# motordriver.net
KiCad netlist of a schematic drawn in EAGLE
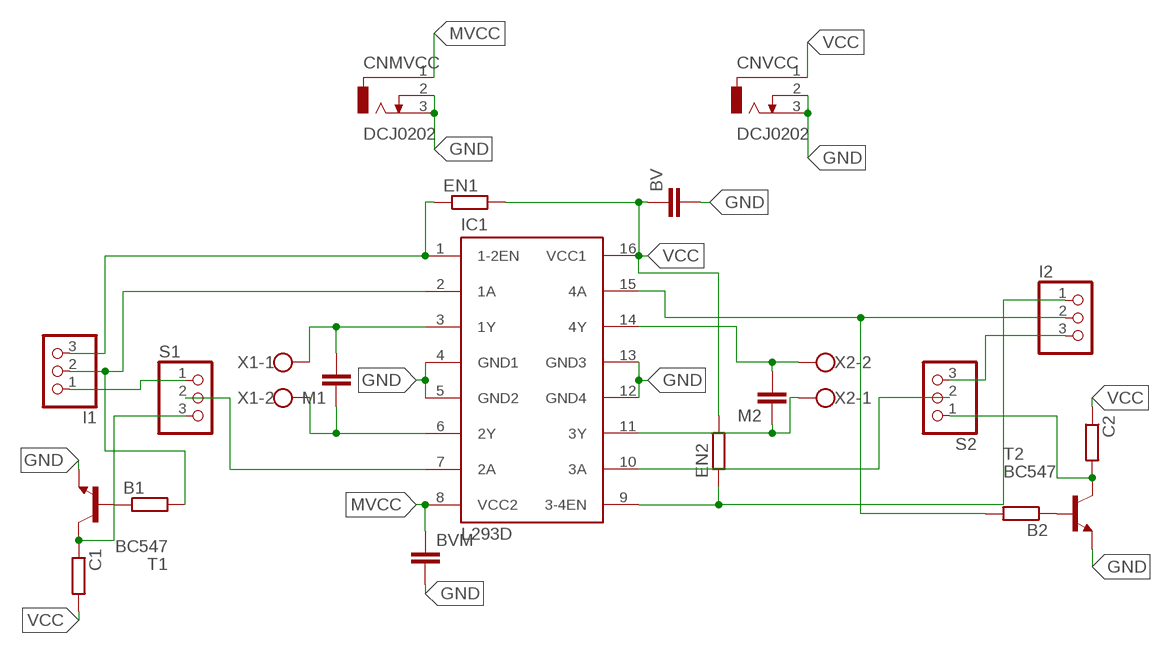
[diagram p0: schematic, sheet 1]

(export (version "E")
  (design (tool "Eeschema 10.0.6"))
  (components
    (comp (ref "B1")
      (value "R-EU_0204/7")
      (footprint "eagle-import:0204_7")
      (libsource (lib "eagle-import") (part "R-EU_0204/7"))
    )
    (comp (ref "B2")
      (value "R-EU_0204/7")
      (footprint "eagle-import:0204_7")
      (libsource (lib "eagle-import") (part "R-EU_0204/7"))
    )
    (comp (ref "BV")
      (value "C2.5/2")
      (footprint "eagle-import:C2.5-2")
      (libsource (lib "eagle-import") (part "C2.5/2"))
    )
    (comp (ref "BVM")
      (value "C-EU050-025X075")
      (footprint "eagle-import:C050-025X075")
      (libsource (lib "eagle-import") (part "C-EU050-025X075"))
    )
    (comp (ref "C1")
      (value "R-EU_0204/7")
      (footprint "eagle-import:0204_7")
      (libsource (lib "eagle-import") (part "R-EU_0204/7"))
    )
    (comp (ref "C2")
      (value "R-EU_0204/7")
      (footprint "eagle-import:0204_7")
      (libsource (lib "eagle-import") (part "R-EU_0204/7"))
    )
    (comp (ref "CNMVCC")
      (value "DCJ0202")
      (footprint "eagle-import:DCJ0202")
      (libsource (lib "eagle-import") (part "DCJ0202"))
    )
    (comp (ref "CNVCC")
      (value "DCJ0202")
      (footprint "eagle-import:DCJ0202")
      (libsource (lib "eagle-import") (part "DCJ0202"))
    )
    (comp (ref "EN1")
      (value "R-EU_0204/7")
      (footprint "eagle-import:0204_7")
      (libsource (lib "eagle-import") (part "R-EU_0204/7"))
    )
    (comp (ref "EN2")
      (value "R-EU_0204/7")
      (footprint "eagle-import:0204_7")
      (libsource (lib "eagle-import") (part "R-EU_0204/7"))
    )
    (comp (ref "I1")
      (value "PINHD-1X3")
      (footprint "eagle-import:1X03")
      (libsource (lib "eagle-import") (part "PINHD-1X3"))
    )
    (comp (ref "I2")
      (value "PINHD-1X3")
      (footprint "eagle-import:1X03")
      (libsource (lib "eagle-import") (part "PINHD-1X3"))
    )
    (comp (ref "IC1")
      (value "L293D")
      (footprint "eagle-import:DIL16")
      (libsource (lib "eagle-import") (part "L293D"))
    )
    (comp (ref "M1")
      (value "C2.5/2")
      (footprint "eagle-import:C2.5-2")
      (libsource (lib "eagle-import") (part "C2.5/2"))
    )
    (comp (ref "M2")
      (value "C2.5/2")
      (footprint "eagle-import:C2.5-2")
      (libsource (lib "eagle-import") (part "C2.5/2"))
    )
    (comp (ref "S1")
      (value "PINHD-1X3")
      (footprint "eagle-import:1X03")
      (libsource (lib "eagle-import") (part "PINHD-1X3"))
    )
    (comp (ref "S2")
      (value "PINHD-1X3")
      (footprint "eagle-import:1X03")
      (libsource (lib "eagle-import") (part "PINHD-1X3"))
    )
    (comp (ref "T1")
      (value "BC547")
      (footprint "eagle-import:TO92")
      (libsource (lib "eagle-import") (part "BC547"))
    )
    (comp (ref "T2")
      (value "BC547")
      (footprint "eagle-import:TO92")
      (libsource (lib "eagle-import") (part "BC547"))
    )
    (comp (ref "X1")
      (value "W237-102")
      (footprint "eagle-import:W237-102")
      (fields (field (name "MPN") "237-102"))
      (libsource (lib "eagle-import") (part "W237-102"))
    )
    (comp (ref "X2")
      (value "W237-102")
      (footprint "eagle-import:W237-102")
      (fields (field (name "MPN") "237-102"))
      (libsource (lib "eagle-import") (part "W237-102"))
    )
  )
  (nets
    (net (code "1") (name "GND") (class "Default")
      (node (ref "BV") (pin "2") (pinfunction "2_2") (pintype "passive"))
      (node (ref "BVM") (pin "2") (pinfunction "2_2") (pintype "passive"))
      (node (ref "CNMVCC") (pin "2") (pinfunction "2_2") (pintype "passive"))
      (node (ref "CNMVCC") (pin "3") (pinfunction "3_3") (pintype "passive"))
      (node (ref "CNVCC") (pin "2") (pinfunction "2_2") (pintype "passive"))
      (node (ref "CNVCC") (pin "3") (pinfunction "3_3") (pintype "passive"))
      (node (ref "IC1") (pin "12") (pinfunction "GND4_12") (pintype "power_in"))
      (node (ref "IC1") (pin "13") (pinfunction "GND3_13") (pintype "power_in"))
      (node (ref "IC1") (pin "4") (pinfunction "GND1_4") (pintype "power_in"))
      (node (ref "IC1") (pin "5") (pinfunction "GND2_5") (pintype "power_in"))
      (node (ref "T1") (pin "1") (pinfunction "E_1") (pintype "passive"))
      (node (ref "T2") (pin "1") (pinfunction "E_1") (pintype "passive"))
    )
    (net (code "2") (name "MVCC") (class "Default")
      (node (ref "BVM") (pin "1") (pinfunction "1_1") (pintype "passive"))
      (node (ref "CNMVCC") (pin "1") (pinfunction "1_1") (pintype "passive"))
      (node (ref "IC1") (pin "8") (pinfunction "VCC2_8") (pintype "power_in"))
    )
    (net (code "3") (name "Net-(I1-Pad1)") (class "Default")
      (node (ref "I1") (pin "1") (pinfunction "1_1") (pintype "passive"))
      (node (ref "S1") (pin "1") (pinfunction "1_1") (pintype "passive"))
    )
    (net (code "4") (name "Net-(I2-Pad3)") (class "Default")
      (node (ref "I2") (pin "3") (pinfunction "3_3") (pintype "passive"))
      (node (ref "S2") (pin "3") (pinfunction "3_3") (pintype "passive"))
    )
    (net (code "5") (name "Net-(IC1-1-2EN)") (class "Default")
      (node (ref "EN1") (pin "1") (pinfunction "1_1") (pintype "passive"))
      (node (ref "I1") (pin "3") (pinfunction "3_3") (pintype "passive"))
      (node (ref "IC1") (pin "1") (pinfunction "1-2EN_1") (pintype "input"))
    )
    (net (code "6") (name "Net-(IC1-1A)") (class "Default")
      (node (ref "B1") (pin "2") (pinfunction "2_2") (pintype "passive"))
      (node (ref "I1") (pin "2") (pinfunction "2_2") (pintype "passive"))
      (node (ref "IC1") (pin "2") (pinfunction "1A_2") (pintype "input"))
    )
    (net (code "7") (name "Net-(IC1-1Y)") (class "Default")
      (node (ref "IC1") (pin "3") (pinfunction "1Y_3") (pintype "output"))
      (node (ref "M1") (pin "2") (pinfunction "2_2") (pintype "passive"))
      (node (ref "X1") (pin "1") (pinfunction "KL_1") (pintype "passive"))
    )
    (net (code "8") (name "Net-(IC1-2A)") (class "Default")
      (node (ref "IC1") (pin "7") (pinfunction "2A_7") (pintype "input"))
      (node (ref "S1") (pin "2") (pinfunction "2_2") (pintype "passive"))
    )
    (net (code "9") (name "Net-(IC1-2Y)") (class "Default")
      (node (ref "IC1") (pin "6") (pinfunction "2Y_6") (pintype "output"))
      (node (ref "M1") (pin "1") (pinfunction "1_1") (pintype "passive"))
      (node (ref "X1") (pin "2") (pinfunction "KL_2") (pintype "passive"))
    )
    (net (code "10") (name "Net-(IC1-3-4EN)") (class "Default")
      (node (ref "EN2") (pin "1") (pinfunction "1_1") (pintype "passive"))
      (node (ref "I2") (pin "1") (pinfunction "1_1") (pintype "passive"))
      (node (ref "IC1") (pin "9") (pinfunction "3-4EN_9") (pintype "input"))
    )
    (net (code "11") (name "Net-(IC1-3A)") (class "Default")
      (node (ref "IC1") (pin "10") (pinfunction "3A_10") (pintype "input"))
      (node (ref "S2") (pin "2") (pinfunction "2_2") (pintype "passive"))
    )
    (net (code "12") (name "Net-(IC1-3Y)") (class "Default")
      (node (ref "IC1") (pin "11") (pinfunction "3Y_11") (pintype "output"))
      (node (ref "M2") (pin "1") (pinfunction "1_1") (pintype "passive"))
      (node (ref "X2") (pin "1") (pinfunction "KL_1") (pintype "passive"))
    )
    (net (code "13") (name "Net-(IC1-4A)") (class "Default")
      (node (ref "B2") (pin "2") (pinfunction "2_2") (pintype "passive"))
      (node (ref "I2") (pin "2") (pinfunction "2_2") (pintype "passive"))
      (node (ref "IC1") (pin "15") (pinfunction "4A_15") (pintype "input"))
    )
    (net (code "14") (name "Net-(IC1-4Y)") (class "Default")
      (node (ref "IC1") (pin "14") (pinfunction "4Y_14") (pintype "output"))
      (node (ref "M2") (pin "2") (pinfunction "2_2") (pintype "passive"))
      (node (ref "X2") (pin "2") (pinfunction "KL_2") (pintype "passive"))
    )
    (net (code "15") (name "Net-(T1-B)") (class "Default")
      (node (ref "B1") (pin "1") (pinfunction "1_1") (pintype "passive"))
      (node (ref "T1") (pin "2") (pinfunction "B_2") (pintype "passive"))
    )
    (net (code "16") (name "Net-(T1-C)") (class "Default")
      (node (ref "C1") (pin "1") (pinfunction "1_1") (pintype "passive"))
      (node (ref "S1") (pin "3") (pinfunction "3_3") (pintype "passive"))
      (node (ref "T1") (pin "3") (pinfunction "C_3") (pintype "passive"))
    )
    (net (code "17") (name "Net-(T2-B)") (class "Default")
      (node (ref "B2") (pin "1") (pinfunction "1_1") (pintype "passive"))
      (node (ref "T2") (pin "2") (pinfunction "B_2") (pintype "passive"))
    )
    (net (code "18") (name "Net-(T2-C)") (class "Default")
      (node (ref "C2") (pin "2") (pinfunction "2_2") (pintype "passive"))
      (node (ref "S2") (pin "1") (pinfunction "1_1") (pintype "passive"))
      (node (ref "T2") (pin "3") (pinfunction "C_3") (pintype "passive"))
    )
    (net (code "19") (name "VCC") (class "Default")
      (node (ref "BV") (pin "1") (pinfunction "1_1") (pintype "passive"))
      (node (ref "C1") (pin "2") (pinfunction "2_2") (pintype "passive"))
      (node (ref "C2") (pin "1") (pinfunction "1_1") (pintype "passive"))
      (node (ref "CNVCC") (pin "1") (pinfunction "1_1") (pintype "passive"))
      (node (ref "EN1") (pin "2") (pinfunction "2_2") (pintype "passive"))
      (node (ref "EN2") (pin "2") (pinfunction "2_2") (pintype "passive"))
      (node (ref "IC1") (pin "16") (pinfunction "VCC1_16") (pintype "power_in"))
    )
  )
)
